# Accelerometer.net
KiCad netlist of a schematic drawn in Altium Designer
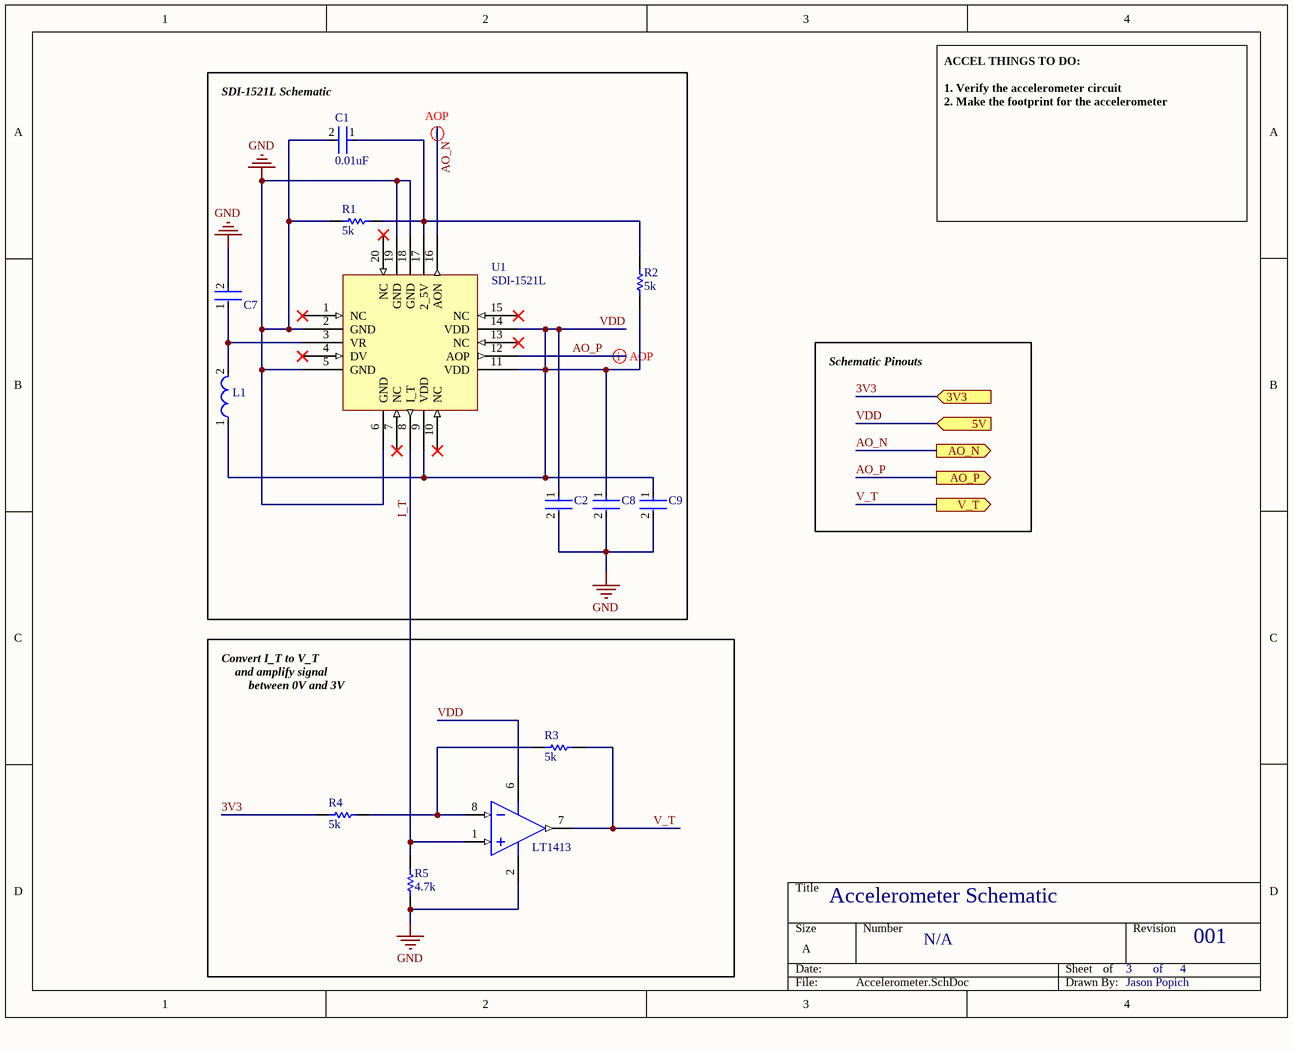
[diagram p0: Accelerometer.SchDoc]

(export (version "E")
  (design (tool "Eeschema 10.0.6"))
  (components
    (comp (ref "C1")
      (value "0.01uF")
      (footprint "FP-GCM21B-0_15-IPC_C")
      (description "Ceramic Capacitor for Automotive 10nF ±1% 50VDC X8G 0805 Embossed T/R (GCM21B5G1H103FA16K)")
      (libsource (lib "Altium Content Vault") (part "02cd4be3c70576c341d710602a673aa"))
    )
    (comp (ref "C2")
      (value "GJ821BR71H105KA12L")
      (footprint "FP-GJ821B-0_1-MFG")
      (description "CAP CER 1UF 50V X7R 0805")
      (fields (field (name "TOLERANCE") "10%"))
      (libsource (lib "Altium Content Vault") (part "02cd4be3c70576c341d710602a673aa"))
    )
    (comp (ref "C7")
      (value "KRM55QR71H106KH01K")
      (footprint "FP-KRM55Q-6_1_5_3_3_9_1_2-MFG")
      (description "Cap Ceramic 10uF 50V X7R ±10% SMD 2220 +125°C Emboss T/R")
      (fields (field (name "TOLERANCE") "10%"))
      (libsource (lib "Altium Content Vault") (part "f23184f103b6ebe33a8c269c53dcba6"))
    )
    (comp (ref "C8")
      (value "GJ821BR71H105KA12L")
      (footprint "FP-GJ821B-0_1-MFG")
      (description "CAP CER 1UF 50V X7R 0805")
      (fields (field (name "TOLERANCE") "10%"))
      (libsource (lib "Altium Content Vault") (part "02cd4be3c70576c341d710602a673aa"))
    )
    (comp (ref "C9")
      (value "GJ821BR71H105KA12L")
      (footprint "FP-GJ821B-0_1-MFG")
      (description "CAP CER 1UF 50V X7R 0805")
      (fields (field (name "TOLERANCE") "10%"))
      (libsource (lib "Altium Content Vault") (part "02cd4be3c70576c341d710602a673aa"))
    )
    (comp (ref "L1")
      (value "LBM2016T330J")
      (footprint "FP-LBM2016-1_6-0_2-IPC_B")
      (description "SMD Inductors 33uH ±5% 0.125A 4.68Ω 0806")
      (fields (field (name "TOLERANCE") "5%"))
      (libsource (lib "Altium Content Vault") (part "725321dda6339637d4d059423bc1c3c"))
    )
    (comp (ref "R1")
      (value "5k")
      (footprint "RESC2013X50X30ML20T20")
      (description "CRCW08055K00FKTA")
      (fields (field (name "MANUFACTURER") "Vishay Dale"))
      (libsource (lib "Altium Content Vault") (part "RES"))
    )
    (comp (ref "R2")
      (value "5k")
      (footprint "RESC2013X50X30ML20T20")
      (description "CRCW08055K00FKTA")
      (fields (field (name "MANUFACTURER") "Vishay Dale"))
      (libsource (lib "Altium Content Vault") (part "RES"))
    )
    (comp (ref "R3")
      (value "5k")
      (footprint "RESC2013X50X30ML20T20")
      (description "CRCW08055K00FKTA")
      (fields (field (name "MANUFACTURER") "Vishay Dale"))
      (libsource (lib "Altium Content Vault") (part "RES"))
    )
    (comp (ref "R4")
      (value "5k")
      (footprint "RESC2013X50X30ML20T20")
      (description "CRCW08055K00FKTA")
      (fields (field (name "MANUFACTURER") "Vishay Dale"))
      (libsource (lib "Altium Content Vault") (part "RES"))
    )
    (comp (ref "R5")
      (value "4.7k")
      (footprint "RESC2013X60X30ML20T20")
      (description "RK73H2ATTD4701F")
      (fields (field (name "MANUFACTURER") "KOA Speer"))
      (libsource (lib "Altium Content Vault") (part "RES"))
    )
    (comp (ref "U1")
      (value "SDI-1521L")
      (footprint "SDI 1521L")
      (description "SDI1521L Accelerometer +/- 2G")
      (libsource (lib "GAINS_SCH") (part "SDI1521L"))
    )
    (comp (ref "U2")
      (value "LT1413")
      (footprint "LT-S8-8_M")
      (fields (field (name "MANUFACTURER") "Linear Technology") (field (name "PARTNUMBER") "LT1413S8#TRPBF"))
      (libsource (lib "Altium Content Vault") (part "LT-LT1413-S8-8"))
    )
  )
  (nets
    (net (code "1") (name "/3V3") (class "Default")
      (node (ref "R4") (pin "2") (pinfunction "2_2") (pintype "passive"))
    )
    (net (code "2") (name "/AO_N") (class "Default")
      (node (ref "U1") (pin "16") (pinfunction "AON_16") (pintype "output"))
    )
    (net (code "3") (name "/AO_P") (class "Default")
      (node (ref "U1") (pin "12") (pinfunction "AOP_12") (pintype "output"))
    )
    (net (code "4") (name "/I_T") (class "Default")
      (node (ref "R5") (pin "2") (pinfunction "2_2") (pintype "passive"))
      (node (ref "U1") (pin "8") (pinfunction "I_T_8") (pintype "output"))
      (node (ref "U2") (pin "1") (pinfunction "+IN_A_1") (pintype "input"))
    )
    (net (code "5") (name "/VDD") (class "Default")
      (node (ref "C2") (pin "1") (pinfunction "1_1") (pintype "passive"))
      (node (ref "C8") (pin "1") (pinfunction "1_1") (pintype "passive"))
      (node (ref "C9") (pin "1") (pinfunction "1_1") (pintype "passive"))
      (node (ref "L1") (pin "1") (pinfunction "1_1") (pintype "passive"))
      (node (ref "R2") (pin "1") (pinfunction "1_1") (pintype "passive"))
      (node (ref "U1") (pin "11") (pinfunction "VDD_11") (pintype "passive"))
      (node (ref "U1") (pin "14") (pinfunction "VDD_14") (pintype "passive"))
      (node (ref "U1") (pin "9") (pinfunction "VDD_9") (pintype "passive"))
      (node (ref "U2") (pin "6") (pinfunction "V+_6") (pintype "passive"))
    )
    (net (code "6") (name "/V_T") (class "Default")
      (node (ref "R3") (pin "1") (pinfunction "1_1") (pintype "passive"))
      (node (ref "U2") (pin "7") (pinfunction "OUT_A_7") (pintype "output"))
    )
    (net (code "7") (name "GND") (class "Default")
      (node (ref "C1") (pin "2") (pinfunction "2_2") (pintype "passive"))
      (node (ref "C2") (pin "2") (pinfunction "2_2") (pintype "passive"))
      (node (ref "C7") (pin "2") (pinfunction "2_2") (pintype "passive"))
      (node (ref "C8") (pin "2") (pinfunction "2_2") (pintype "passive"))
      (node (ref "C9") (pin "2") (pinfunction "2_2") (pintype "passive"))
      (node (ref "R1") (pin "2") (pinfunction "2_2") (pintype "passive"))
      (node (ref "R5") (pin "1") (pinfunction "1_1") (pintype "passive"))
      (node (ref "U1") (pin "18") (pinfunction "GND_18") (pintype "passive"))
      (node (ref "U1") (pin "19") (pinfunction "GND_19") (pintype "passive"))
      (node (ref "U1") (pin "2") (pinfunction "GND_2") (pintype "passive"))
      (node (ref "U1") (pin "5") (pinfunction "GND_5") (pintype "passive"))
      (node (ref "U1") (pin "6") (pinfunction "GND_6") (pintype "passive"))
      (node (ref "U2") (pin "2") (pinfunction "V-_2") (pintype "passive"))
    )
    (net (code "8") (name "Net-(U1-2_5V)") (class "Default")
      (node (ref "C1") (pin "1") (pinfunction "1_1") (pintype "passive"))
      (node (ref "R1") (pin "1") (pinfunction "1_1") (pintype "passive"))
      (node (ref "R2") (pin "2") (pinfunction "2_2") (pintype "passive"))
      (node (ref "U1") (pin "17") (pinfunction "2_5V_17") (pintype "passive"))
    )
    (net (code "9") (name "Net-(U1-VR)") (class "Default")
      (node (ref "C7") (pin "1") (pinfunction "1_1") (pintype "passive"))
      (node (ref "L1") (pin "2") (pinfunction "2_2") (pintype "passive"))
      (node (ref "U1") (pin "3") (pinfunction "VR_3") (pintype "passive"))
    )
    (net (code "10") (name "Net-(U2A--IN_A)") (class "Default")
      (node (ref "R3") (pin "2") (pinfunction "2_2") (pintype "passive"))
      (node (ref "R4") (pin "1") (pinfunction "1_1") (pintype "passive"))
      (node (ref "U2") (pin "8") (pinfunction "-IN_A_8") (pintype "input"))
    )
    (net (code "11") (name "unconnected-(U1-DV-Pad4)") (class "Default")
      (node (ref "U1") (pin "4") (pinfunction "DV_4") (pintype "input+no_connect"))
    )
    (net (code "12") (name "unconnected-(U1-NC-Pad1)") (class "Default")
      (node (ref "U1") (pin "1") (pinfunction "NC_1") (pintype "input+no_connect"))
    )
    (net (code "13") (name "unconnected-(U1-NC-Pad7)") (class "Default")
      (node (ref "U1") (pin "7") (pinfunction "NC_7") (pintype "input+no_connect"))
    )
    (net (code "14") (name "unconnected-(U1-NC-Pad10)") (class "Default")
      (node (ref "U1") (pin "10") (pinfunction "NC_10") (pintype "input+no_connect"))
    )
    (net (code "15") (name "unconnected-(U1-NC-Pad13)") (class "Default")
      (node (ref "U1") (pin "13") (pinfunction "NC_13") (pintype "input+no_connect"))
    )
    (net (code "16") (name "unconnected-(U1-NC-Pad15)") (class "Default")
      (node (ref "U1") (pin "15") (pinfunction "NC_15") (pintype "input+no_connect"))
    )
    (net (code "17") (name "unconnected-(U1-NC-Pad20)") (class "Default")
      (node (ref "U1") (pin "20") (pinfunction "NC_20") (pintype "input+no_connect"))
    )
  )
)
